# TestSensorE469.net
KiCad netlist of a schematic drawn in EasyEDA
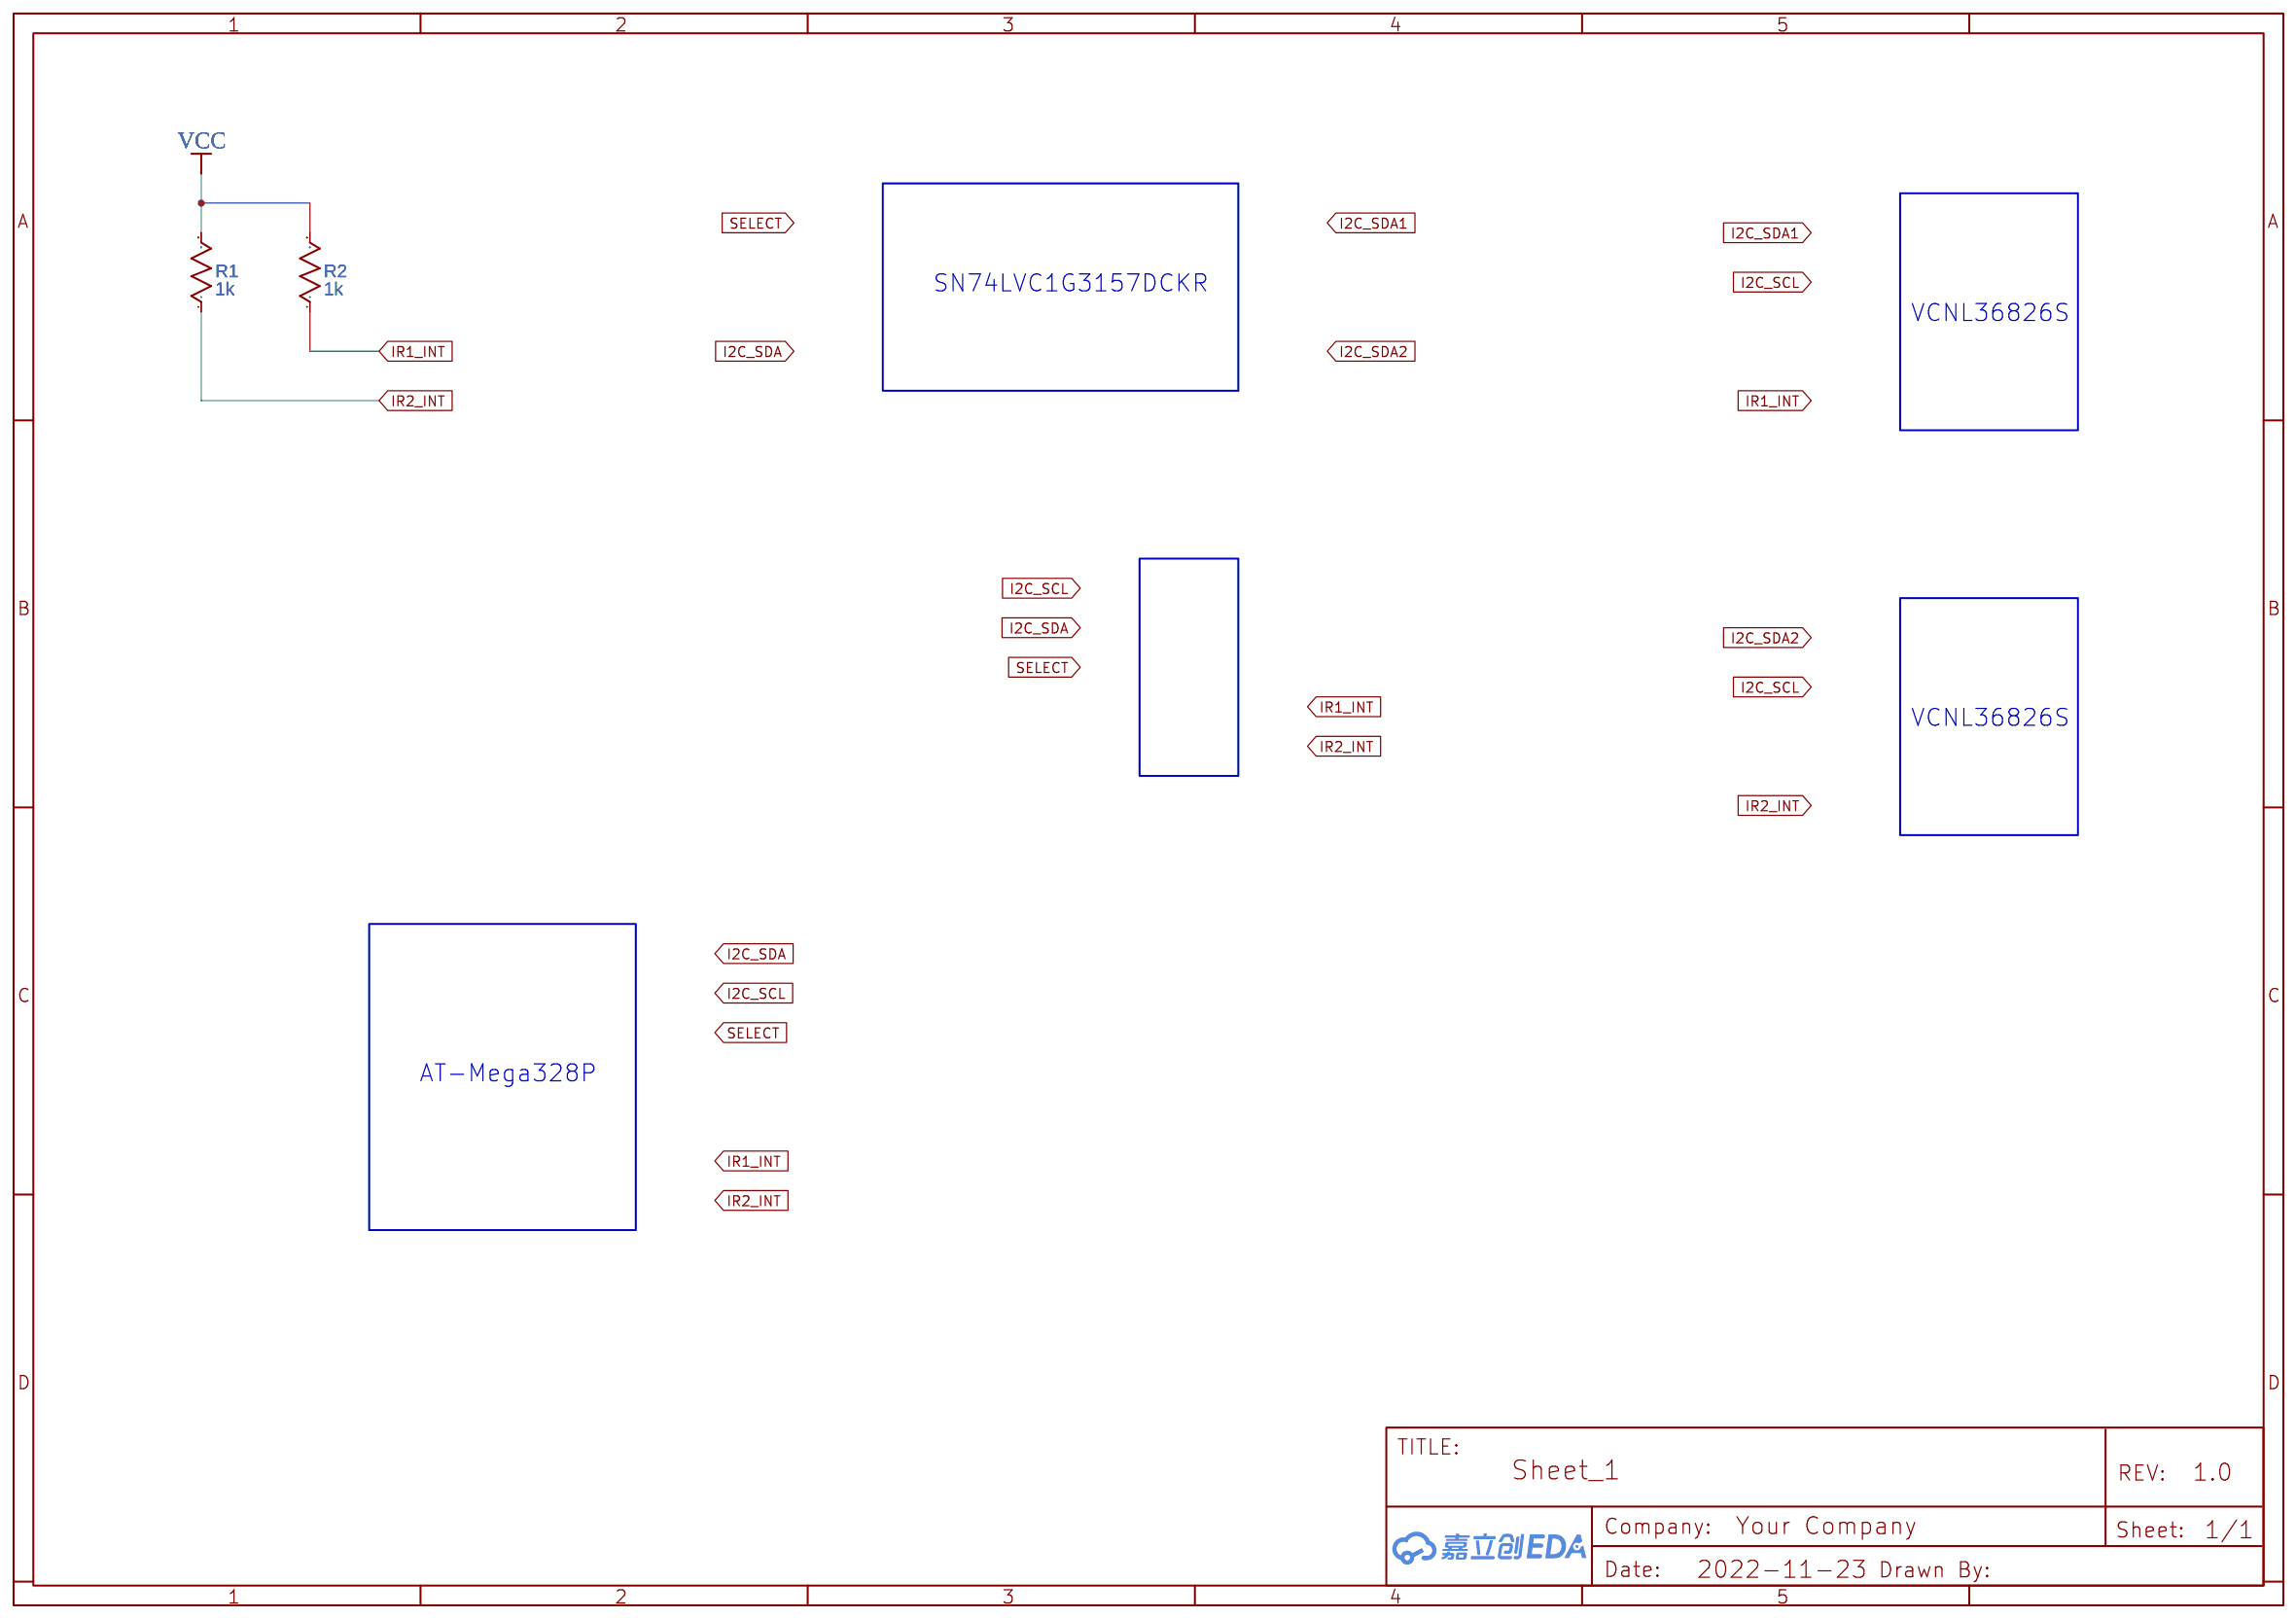
[diagram p0: schematic sheet]

(export (version "E")
  (design (tool "Eeschema 10.0.6"))
  (components
    (comp (ref "R1") (value "1k") (libsource (lib "") (part "R_0603_US")))
    (comp (ref "R2") (value "1k") (libsource (lib "") (part "R_0603_US")))
  )
  (nets
    (net (code "5") (name "IR1_INT") (class "Default")
      (node (ref "R2") (pin "1") (pinfunction "1_1") (pintype "unspecified"))
    )
    (net (code "6") (name "IR2_INT") (class "Default")
      (node (ref "R1") (pin "1") (pinfunction "1_1") (pintype "unspecified"))
    )
    (net (code "8") (name "VCC") (class "Default")
      (node (ref "R1") (pin "2") (pinfunction "2_2") (pintype "unspecified"))
      (node (ref "R2") (pin "2") (pinfunction "2_2") (pintype "unspecified"))
    )
  )
)
